# gatedriver_trafo_sma_compact_ACDC_smd.net
KiCad netlist of a schematic drawn in EAGLE
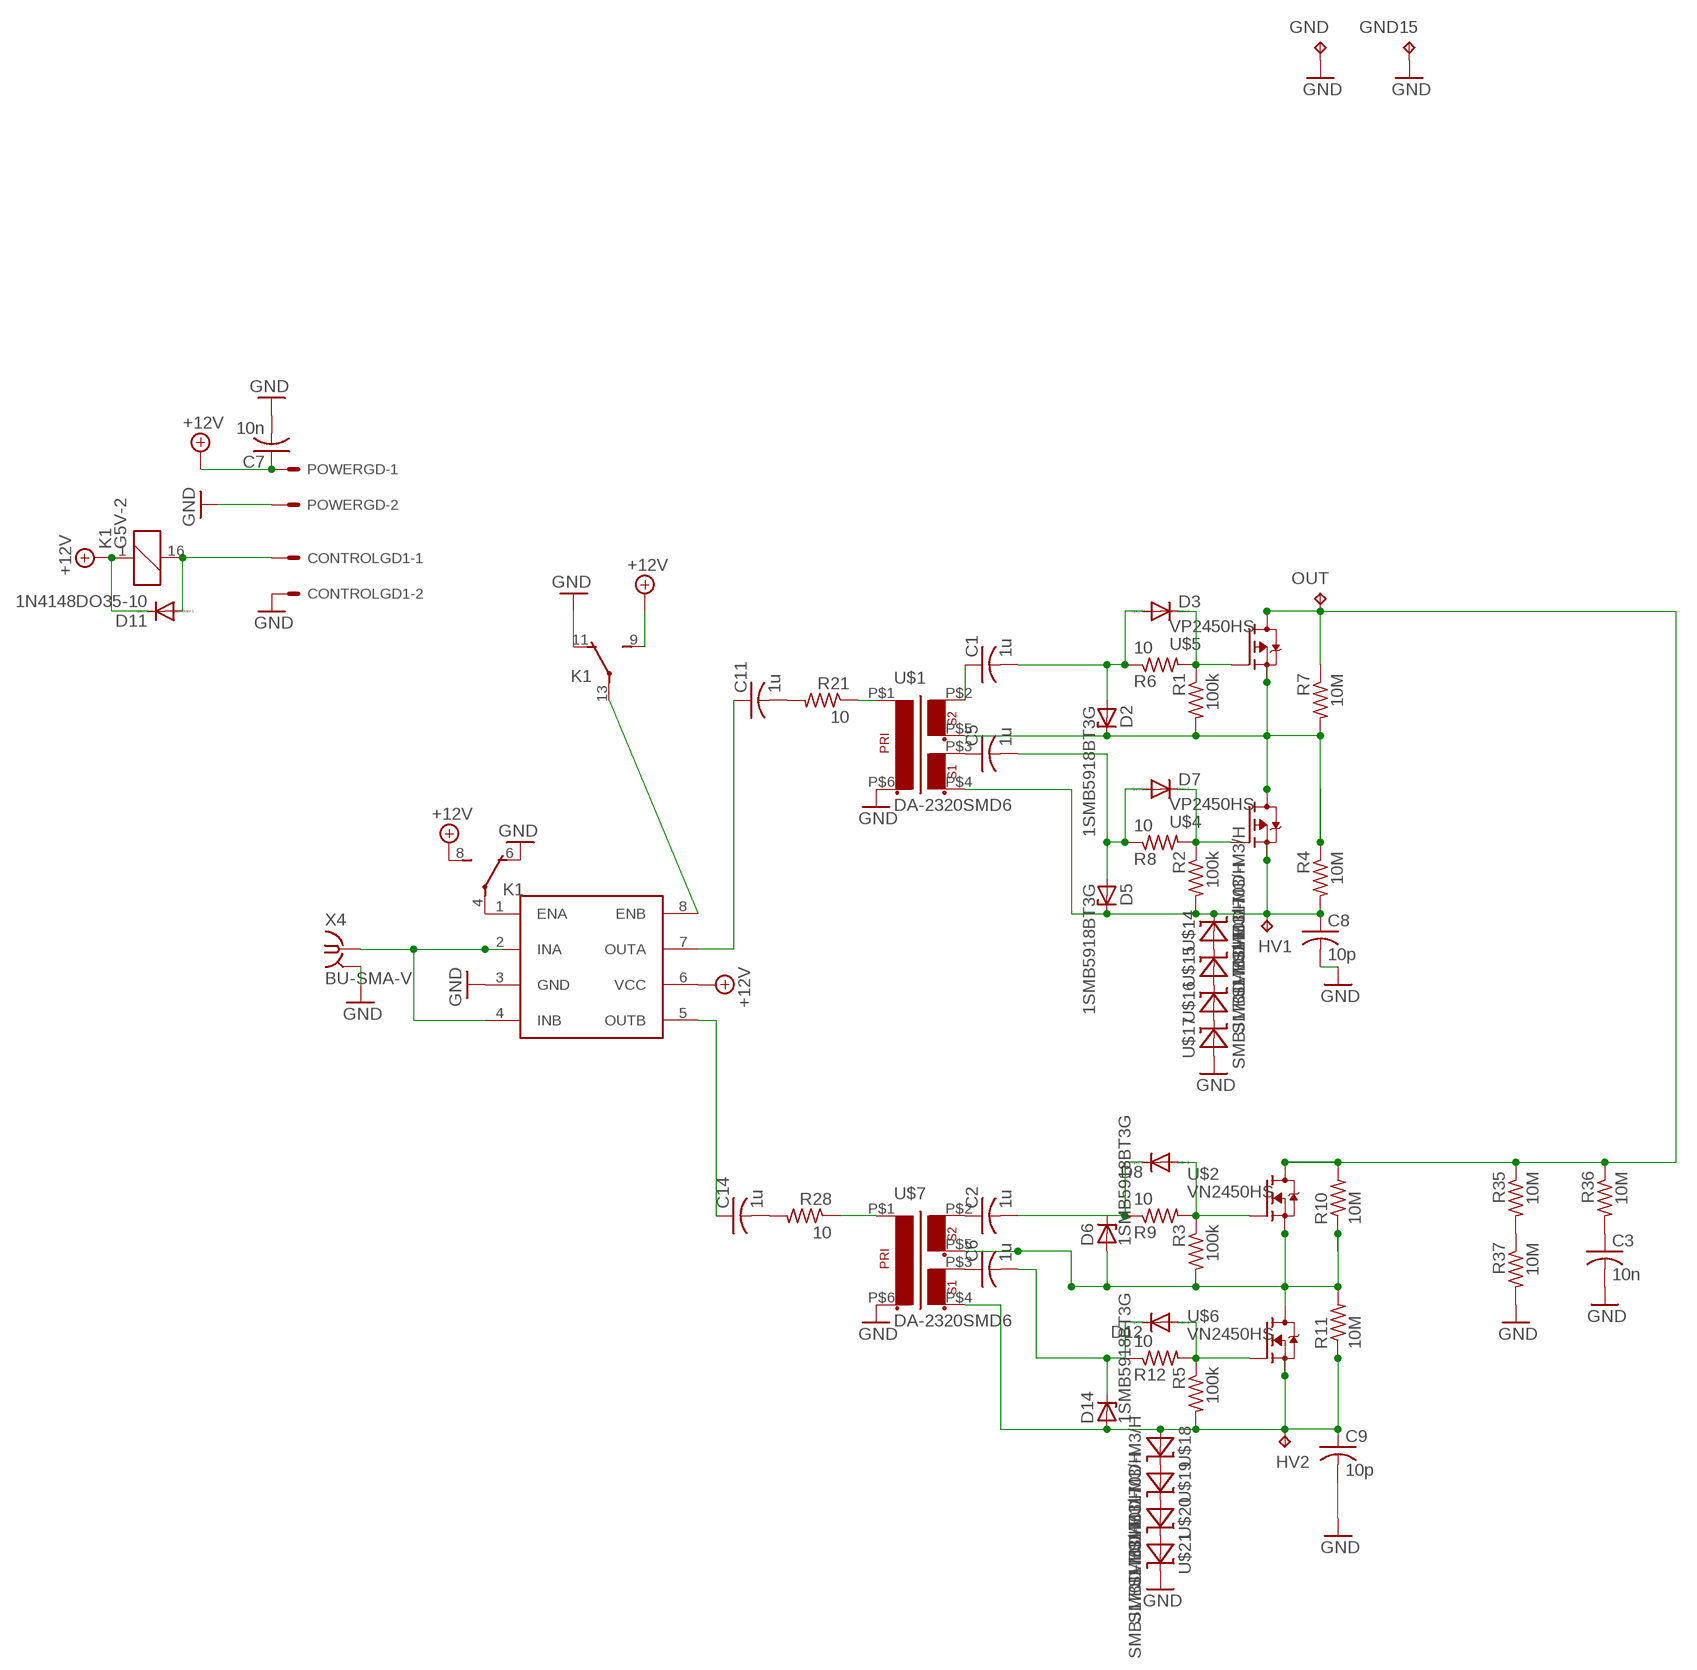
[diagram p0: schematic, sheet 1]

(export (version "E")
  (design (tool "Eeschema 10.0.6"))
  (components
    (comp (ref "C1")
      (value "1u")
      (footprint "eagle-import:C0805")
      (libsource (lib "eagle-import") (part "resistor_C-USC0805"))
    )
    (comp (ref "C2")
      (value "1u")
      (footprint "eagle-import:C0805")
      (libsource (lib "eagle-import") (part "resistor_C-USC0805"))
    )
    (comp (ref "C3")
      (value "10n")
      (footprint "eagle-import:C0805")
      (libsource (lib "eagle-import") (part "resistor_C-USC0805"))
    )
    (comp (ref "C5")
      (value "1u")
      (footprint "eagle-import:C0805")
      (libsource (lib "eagle-import") (part "resistor_C-USC0805"))
    )
    (comp (ref "C6")
      (value "1u")
      (footprint "eagle-import:C0805")
      (libsource (lib "eagle-import") (part "resistor_C-USC0805"))
    )
    (comp (ref "C7")
      (value "10n")
      (footprint "eagle-import:C050-030X075")
      (libsource (lib "eagle-import") (part "C-US050-030X075"))
    )
    (comp (ref "C8")
      (value "10p")
      (footprint "eagle-import:C102-064X133")
      (libsource (lib "eagle-import") (part "resistor_C-US102-064X133"))
    )
    (comp (ref "C9")
      (value "10p")
      (footprint "eagle-import:C102-064X133")
      (libsource (lib "eagle-import") (part "resistor_C-US102-064X133"))
    )
    (comp (ref "C11")
      (value "1u")
      (footprint "eagle-import:C0805")
      (libsource (lib "eagle-import") (part "resistor_C-USC0805"))
    )
    (comp (ref "C14")
      (value "1u")
      (footprint "eagle-import:C0805")
      (libsource (lib "eagle-import") (part "resistor_C-USC0805"))
    )
    (comp (ref "CONTROLGD1")
      (value "KK-156-2")
      (footprint "eagle-import:KK-156-2")
      (libsource (lib "eagle-import") (part "KK-156-2"))
    )
    (comp (ref "D2")
      (value "1SMB5918BT3G")
      (footprint "eagle-import:SMB")
      (libsource (lib "eagle-import") (part "ZENER-DIODESMB"))
    )
    (comp (ref "D3")
      (value "DIODE-SMB")
      (footprint "eagle-import:SMB")
      (libsource (lib "eagle-import") (part "DIODE-SMB"))
    )
    (comp (ref "D5")
      (value "1SMB5918BT3G")
      (footprint "eagle-import:SMB")
      (libsource (lib "eagle-import") (part "ZENER-DIODESMB"))
    )
    (comp (ref "D6")
      (value "1SMB5918BT3G")
      (footprint "eagle-import:SMB")
      (libsource (lib "eagle-import") (part "ZENER-DIODESMB"))
    )
    (comp (ref "D7")
      (value "DIODE-SMB")
      (footprint "eagle-import:SMB")
      (libsource (lib "eagle-import") (part "DIODE-SMB"))
    )
    (comp (ref "D8")
      (value "DIODE-SMB")
      (footprint "eagle-import:SMB")
      (libsource (lib "eagle-import") (part "DIODE-SMB"))
    )
    (comp (ref "D11")
      (value "1N4148DO35-10")
      (footprint "eagle-import:DO35-10")
      (libsource (lib "eagle-import") (part "1N4148DO35-10"))
    )
    (comp (ref "D12")
      (value "DIODE-SMB")
      (footprint "eagle-import:SMB")
      (libsource (lib "eagle-import") (part "DIODE-SMB"))
    )
    (comp (ref "D14")
      (value "1SMB5918BT3G")
      (footprint "eagle-import:SMB")
      (libsource (lib "eagle-import") (part "ZENER-DIODESMB"))
    )
    (comp (ref "GND")
      (value "TPPAD1-20Y")
      (footprint "eagle-import:P1-20Y")
      (libsource (lib "eagle-import") (part "TPPAD1-20Y"))
    )
    (comp (ref "GND15")
      (value "TPPAD1-20Y")
      (footprint "eagle-import:P1-20Y")
      (libsource (lib "eagle-import") (part "TPPAD1-20Y"))
    )
    (comp (ref "HV1")
      (value "TPPAD1-20Y")
      (footprint "eagle-import:P1-20Y")
      (libsource (lib "eagle-import") (part "TPPAD1-20Y"))
    )
    (comp (ref "HV2")
      (value "TPPAD1-20Y")
      (footprint "eagle-import:P1-20Y")
      (libsource (lib "eagle-import") (part "TPPAD1-20Y"))
    )
    (comp (ref "K1")
      (value "G5V-2")
      (footprint "eagle-import:G5V-2")
      (fields (field (name "MPN") "G5V-2 5DC"))
      (libsource (lib "eagle-import") (part "G5V-2"))
    )
    (comp (ref "OUT")
      (value "TPPAD1-20Y")
      (footprint "eagle-import:P1-20Y")
      (libsource (lib "eagle-import") (part "TPPAD1-20Y"))
    )
    (comp (ref "POWERGD")
      (value "KK-156-2")
      (footprint "eagle-import:KK-156-2")
      (libsource (lib "eagle-import") (part "KK-156-2"))
    )
    (comp (ref "R1")
      (value "100k")
      (footprint "eagle-import:R0805")
      (libsource (lib "eagle-import") (part "R-US_R0805"))
    )
    (comp (ref "R2")
      (value "100k")
      (footprint "eagle-import:R0805")
      (libsource (lib "eagle-import") (part "R-US_R0805"))
    )
    (comp (ref "R3")
      (value "100k")
      (footprint "eagle-import:R0805")
      (libsource (lib "eagle-import") (part "R-US_R0805"))
    )
    (comp (ref "R4")
      (value "10M")
      (footprint "eagle-import:R2512")
      (libsource (lib "eagle-import") (part "R-US_R2512"))
    )
    (comp (ref "R5")
      (value "100k")
      (footprint "eagle-import:R0805")
      (libsource (lib "eagle-import") (part "R-US_R0805"))
    )
    (comp (ref "R6")
      (value "10")
      (footprint "eagle-import:R0805")
      (libsource (lib "eagle-import") (part "R-US_R0805"))
    )
    (comp (ref "R7")
      (value "10M")
      (footprint "eagle-import:R2512")
      (libsource (lib "eagle-import") (part "R-US_R2512"))
    )
    (comp (ref "R8")
      (value "10")
      (footprint "eagle-import:R0805")
      (libsource (lib "eagle-import") (part "R-US_R0805"))
    )
    (comp (ref "R9")
      (value "10")
      (footprint "eagle-import:R0805")
      (libsource (lib "eagle-import") (part "R-US_R0805"))
    )
    (comp (ref "R10")
      (value "10M")
      (footprint "eagle-import:R2512")
      (libsource (lib "eagle-import") (part "R-US_R2512"))
    )
    (comp (ref "R11")
      (value "10M")
      (footprint "eagle-import:R2512")
      (libsource (lib "eagle-import") (part "R-US_R2512"))
    )
    (comp (ref "R12")
      (value "10")
      (footprint "eagle-import:R0805")
      (libsource (lib "eagle-import") (part "R-US_R0805"))
    )
    (comp (ref "R21")
      (value "10")
      (footprint "eagle-import:R0805")
      (libsource (lib "eagle-import") (part "R-US_R0805"))
    )
    (comp (ref "R28")
      (value "10")
      (footprint "eagle-import:R0805")
      (libsource (lib "eagle-import") (part "R-US_R0805"))
    )
    (comp (ref "R35")
      (value "10M")
      (footprint "eagle-import:R2512")
      (libsource (lib "eagle-import") (part "R-US_R2512"))
    )
    (comp (ref "R36")
      (value "10M")
      (footprint "eagle-import:R2512")
      (libsource (lib "eagle-import") (part "R-US_R2512"))
    )
    (comp (ref "R37")
      (value "10M")
      (footprint "eagle-import:R2512")
      (libsource (lib "eagle-import") (part "R-US_R2512"))
    )
    (comp (ref "U$1")
      (value "DA-2320SMD6")
      (footprint "eagle-import:SMD6")
      (libsource (lib "eagle-import") (part "DA-2320SMD6"))
    )
    (comp (ref "U$2")
      (value "VN2450HS")
      (footprint "eagle-import:SO89_HS")
      (libsource (lib "eagle-import") (part "VN2450HS"))
    )
    (comp (ref "U$3")
      (value "UCC27425")
      (footprint "eagle-import:DIL08")
      (libsource (lib "eagle-import") (part "UCC27425"))
    )
    (comp (ref "U$4")
      (value "VP2450HS")
      (footprint "eagle-import:SO89_HS")
      (libsource (lib "eagle-import") (part "VP2450HS"))
    )
    (comp (ref "U$5")
      (value "VP2450HS")
      (footprint "eagle-import:SO89_HS")
      (libsource (lib "eagle-import") (part "VP2450HS"))
    )
    (comp (ref "U$6")
      (value "VN2450HS")
      (footprint "eagle-import:SO89_HS")
      (libsource (lib "eagle-import") (part "VN2450HS"))
    )
    (comp (ref "U$7")
      (value "DA-2320SMD6")
      (footprint "eagle-import:SMD6")
      (libsource (lib "eagle-import") (part "DA-2320SMD6"))
    )
    (comp (ref "U$14")
      (value "SMBJ170D-M3/H")
      (footprint "eagle-import:DO214AA")
      (libsource (lib "eagle-import") (part "SMBJ170D-M3/H"))
    )
    (comp (ref "U$15")
      (value "SMBJ170D-M3/H")
      (footprint "eagle-import:DO214AA")
      (libsource (lib "eagle-import") (part "SMBJ170D-M3/H"))
    )
    (comp (ref "U$16")
      (value "SMBJ170D-M3/H")
      (footprint "eagle-import:DO214AA")
      (libsource (lib "eagle-import") (part "SMBJ170D-M3/H"))
    )
    (comp (ref "U$17")
      (value "SMBJ170D-M3/H")
      (footprint "eagle-import:DO214AA")
      (libsource (lib "eagle-import") (part "SMBJ170D-M3/H"))
    )
    (comp (ref "U$18")
      (value "SMBJ170D-M3/H")
      (footprint "eagle-import:DO214AA")
      (libsource (lib "eagle-import") (part "SMBJ170D-M3/H"))
    )
    (comp (ref "U$19")
      (value "SMBJ170D-M3/H")
      (footprint "eagle-import:DO214AA")
      (libsource (lib "eagle-import") (part "SMBJ170D-M3/H"))
    )
    (comp (ref "U$20")
      (value "SMBJ170D-M3/H")
      (footprint "eagle-import:DO214AA")
      (libsource (lib "eagle-import") (part "SMBJ170D-M3/H"))
    )
    (comp (ref "U$21")
      (value "SMBJ170D-M3/H")
      (footprint "eagle-import:DO214AA")
      (libsource (lib "eagle-import") (part "SMBJ170D-M3/H"))
    )
    (comp (ref "X4")
      (value "BU-SMA-V")
      (footprint "eagle-import:BU-SMA-V")
      (libsource (lib "eagle-import") (part "BU-SMA-V"))
    )
  )
  (nets
    (net (code "1") (name "+12V") (class "Default")
      (node (ref "C7") (pin "1") (pinfunction "1_1") (pintype "passive"))
      (node (ref "D11") (pin "C") (pinfunction "C_C") (pintype "passive"))
      (node (ref "K1") (pin "1") (pinfunction "1_1") (pintype "passive"))
      (node (ref "K1") (pin "8") (pinfunction "S_8") (pintype "passive"))
      (node (ref "K1") (pin "9") (pinfunction "S_9") (pintype "passive"))
      (node (ref "POWERGD") (pin "1") (pinfunction "S_1") (pintype "passive"))
      (node (ref "U$3") (pin "6") (pinfunction "VCC_6") (pintype "bidirectional"))
    )
    (net (code "2") (name "GND") (class "Default")
      (node (ref "C3") (pin "2") (pinfunction "2_2") (pintype "passive"))
      (node (ref "C7") (pin "2") (pinfunction "2_2") (pintype "passive"))
      (node (ref "C8") (pin "2") (pinfunction "2_2") (pintype "passive"))
      (node (ref "C9") (pin "2") (pinfunction "2_2") (pintype "passive"))
      (node (ref "CONTROLGD1") (pin "2") (pinfunction "S_2") (pintype "passive"))
      (node (ref "GND") (pin "TP") (pinfunction "TP_TP") (pintype "input"))
      (node (ref "GND15") (pin "TP") (pinfunction "TP_TP") (pintype "input"))
      (node (ref "K1") (pin "11") (pinfunction "O_11") (pintype "passive"))
      (node (ref "K1") (pin "6") (pinfunction "O_6") (pintype "passive"))
      (node (ref "POWERGD") (pin "2") (pinfunction "S_2") (pintype "passive"))
      (node (ref "R37") (pin "2") (pinfunction "2_2") (pintype "passive"))
      (node (ref "U$1") (pin "P$6") (pinfunction "2_P$6") (pintype "passive"))
      (node (ref "U$17") (pin "A") (pinfunction "A_A") (pintype "passive"))
      (node (ref "U$21") (pin "C") (pinfunction "C_C") (pintype "passive"))
      (node (ref "U$3") (pin "3") (pinfunction "GND_3") (pintype "bidirectional"))
      (node (ref "U$7") (pin "P$6") (pinfunction "2_P$6") (pintype "passive"))
      (node (ref "X4") (pin "2") (pinfunction "2_2") (pintype "passive"))
      (node (ref "X4") (pin "3") (pinfunction "2_3") (pintype "passive"))
      (node (ref "X4") (pin "4") (pinfunction "2_4") (pintype "passive"))
      (node (ref "X4") (pin "5") (pinfunction "2_5") (pintype "passive"))
    )
    (net (code "3") (name "Net-(C1-Pad2)") (class "Default")
      (node (ref "C1") (pin "2") (pinfunction "2_2") (pintype "passive"))
      (node (ref "D2") (pin "A") (pinfunction "A_A") (pintype "passive"))
      (node (ref "D3") (pin "A") (pinfunction "A_A") (pintype "passive"))
      (node (ref "R6") (pin "1") (pinfunction "1_1") (pintype "passive"))
    )
    (net (code "4") (name "Net-(C2-Pad2)") (class "Default")
      (node (ref "C2") (pin "2") (pinfunction "2_2") (pintype "passive"))
      (node (ref "D6") (pin "C") (pinfunction "C_C") (pintype "passive"))
      (node (ref "D8") (pin "C") (pinfunction "C_C") (pintype "passive"))
      (node (ref "R9") (pin "1") (pinfunction "1_1") (pintype "passive"))
    )
    (net (code "5") (name "Net-(C3-Pad1)") (class "Default")
      (node (ref "C3") (pin "1") (pinfunction "1_1") (pintype "passive"))
      (node (ref "R36") (pin "2") (pinfunction "2_2") (pintype "passive"))
    )
    (net (code "6") (name "Net-(C5-Pad2)") (class "Default")
      (node (ref "C5") (pin "2") (pinfunction "2_2") (pintype "passive"))
      (node (ref "D5") (pin "A") (pinfunction "A_A") (pintype "passive"))
      (node (ref "D7") (pin "A") (pinfunction "A_A") (pintype "passive"))
      (node (ref "R8") (pin "1") (pinfunction "1_1") (pintype "passive"))
    )
    (net (code "7") (name "Net-(C6-Pad2)") (class "Default")
      (node (ref "C6") (pin "2") (pinfunction "2_2") (pintype "passive"))
      (node (ref "D12") (pin "C") (pinfunction "C_C") (pintype "passive"))
      (node (ref "D14") (pin "C") (pinfunction "C_C") (pintype "passive"))
      (node (ref "R12") (pin "1") (pinfunction "1_1") (pintype "passive"))
    )
    (net (code "8") (name "Net-(C11-Pad2)") (class "Default")
      (node (ref "C11") (pin "2") (pinfunction "2_2") (pintype "passive"))
      (node (ref "R21") (pin "2") (pinfunction "2_2") (pintype "passive"))
    )
    (net (code "9") (name "Net-(C14-Pad2)") (class "Default")
      (node (ref "C14") (pin "2") (pinfunction "2_2") (pintype "passive"))
      (node (ref "R28") (pin "2") (pinfunction "2_2") (pintype "passive"))
    )
    (net (code "10") (name "Net-(CONTROLGD1A-S)") (class "Default")
      (node (ref "CONTROLGD1") (pin "1") (pinfunction "S_1") (pintype "passive"))
      (node (ref "D11") (pin "A") (pinfunction "A_A") (pintype "passive"))
      (node (ref "K1") (pin "16") (pinfunction "2_16") (pintype "passive"))
    )
    (net (code "11") (name "Net-(K1A-P)") (class "Default")
      (node (ref "K1") (pin "4") (pinfunction "P_4") (pintype "passive"))
      (node (ref "U$3") (pin "1") (pinfunction "ENA_1") (pintype "bidirectional"))
    )
    (net (code "12") (name "Net-(K1B-P)") (class "Default")
      (node (ref "K1") (pin "13") (pinfunction "P_13") (pintype "passive"))
      (node (ref "U$3") (pin "8") (pinfunction "ENB_8") (pintype "bidirectional"))
    )
    (net (code "13") (name "Net-(OUT-PadTP)") (class "Default")
      (node (ref "OUT") (pin "TP") (pinfunction "TP_TP") (pintype "input"))
      (node (ref "R10") (pin "2") (pinfunction "2_2") (pintype "passive"))
      (node (ref "R35") (pin "1") (pinfunction "1_1") (pintype "passive"))
      (node (ref "R36") (pin "1") (pinfunction "1_1") (pintype "passive"))
      (node (ref "R7") (pin "1") (pinfunction "1_1") (pintype "passive"))
      (node (ref "U$2") (pin "C") (pinfunction "D_C") (pintype "passive"))
      (node (ref "U$2") (pin "C@1") (pinfunction "D_C@1") (pintype "passive"))
      (node (ref "U$5") (pin "C") (pinfunction "D_C") (pintype "passive"))
      (node (ref "U$5") (pin "C@1") (pinfunction "D_C@1") (pintype "passive"))
    )
    (net (code "14") (name "Net-(R35-Pad2)") (class "Default")
      (node (ref "R35") (pin "2") (pinfunction "2_2") (pintype "passive"))
      (node (ref "R37") (pin "1") (pinfunction "1_1") (pintype "passive"))
    )
    (net (code "15") (name "Net-(U$1-1)") (class "Default")
      (node (ref "R21") (pin "1") (pinfunction "1_1") (pintype "passive"))
      (node (ref "U$1") (pin "P$1") (pinfunction "1_P$1") (pintype "passive"))
    )
    (net (code "16") (name "Net-(U$1-3)") (class "Default")
      (node (ref "C8") (pin "1") (pinfunction "1_1") (pintype "passive"))
      (node (ref "D5") (pin "C") (pinfunction "C_C") (pintype "passive"))
      (node (ref "HV1") (pin "TP") (pinfunction "TP_TP") (pintype "input"))
      (node (ref "R2") (pin "2") (pinfunction "2_2") (pintype "passive"))
      (node (ref "R4") (pin "2") (pinfunction "2_2") (pintype "passive"))
      (node (ref "U$1") (pin "P$4") (pinfunction "3_P$4") (pintype "passive"))
      (node (ref "U$14") (pin "C") (pinfunction "C_C") (pintype "passive"))
      (node (ref "U$4") (pin "E") (pinfunction "S_E") (pintype "passive"))
    )
    (net (code "17") (name "Net-(U$1-4)") (class "Default")
      (node (ref "C5") (pin "1") (pinfunction "1_1") (pintype "passive"))
      (node (ref "U$1") (pin "P$3") (pinfunction "4_P$3") (pintype "passive"))
    )
    (net (code "18") (name "Net-(U$1-5)") (class "Default")
      (node (ref "D2") (pin "C") (pinfunction "C_C") (pintype "passive"))
      (node (ref "R1") (pin "2") (pinfunction "2_2") (pintype "passive"))
      (node (ref "R4") (pin "1") (pinfunction "1_1") (pintype "passive"))
      (node (ref "R7") (pin "2") (pinfunction "2_2") (pintype "passive"))
      (node (ref "U$1") (pin "P$5") (pinfunction "5_P$5") (pintype "passive"))
      (node (ref "U$4") (pin "C") (pinfunction "D_C") (pintype "passive"))
      (node (ref "U$4") (pin "C@1") (pinfunction "D_C@1") (pintype "passive"))
      (node (ref "U$5") (pin "E") (pinfunction "S_E") (pintype "passive"))
    )
    (net (code "19") (name "Net-(U$1-6)") (class "Default")
      (node (ref "C1") (pin "1") (pinfunction "1_1") (pintype "passive"))
      (node (ref "U$1") (pin "P$2") (pinfunction "6_P$2") (pintype "passive"))
    )
    (net (code "20") (name "Net-(U$2-G)") (class "Default")
      (node (ref "D8") (pin "A") (pinfunction "A_A") (pintype "passive"))
      (node (ref "R3") (pin "1") (pinfunction "1_1") (pintype "passive"))
      (node (ref "R9") (pin "2") (pinfunction "2_2") (pintype "passive"))
      (node (ref "U$2") (pin "B") (pinfunction "G_B") (pintype "passive"))
    )
    (net (code "21") (name "Net-(U$2-S)") (class "Default")
      (node (ref "D6") (pin "A") (pinfunction "A_A") (pintype "passive"))
      (node (ref "R10") (pin "1") (pinfunction "1_1") (pintype "passive"))
      (node (ref "R11") (pin "2") (pinfunction "2_2") (pintype "passive"))
      (node (ref "R3") (pin "2") (pinfunction "2_2") (pintype "passive"))
      (node (ref "U$2") (pin "E") (pinfunction "S_E") (pintype "passive"))
      (node (ref "U$6") (pin "C") (pinfunction "D_C") (pintype "passive"))
      (node (ref "U$6") (pin "C@1") (pinfunction "D_C@1") (pintype "passive"))
      (node (ref "U$7") (pin "P$5") (pinfunction "5_P$5") (pintype "passive"))
    )
    (net (code "22") (name "Net-(U$3-INA)") (class "Default")
      (node (ref "U$3") (pin "2") (pinfunction "INA_2") (pintype "bidirectional"))
      (node (ref "U$3") (pin "4") (pinfunction "INB_4") (pintype "bidirectional"))
      (node (ref "X4") (pin "1") (pinfunction "1_1") (pintype "passive"))
    )
    (net (code "23") (name "Net-(U$3-OUTA)") (class "Default")
      (node (ref "C11") (pin "1") (pinfunction "1_1") (pintype "passive"))
      (node (ref "U$3") (pin "7") (pinfunction "OUTA_7") (pintype "bidirectional"))
    )
    (net (code "24") (name "Net-(U$3-OUTB)") (class "Default")
      (node (ref "C14") (pin "1") (pinfunction "1_1") (pintype "passive"))
      (node (ref "U$3") (pin "5") (pinfunction "OUTB_5") (pintype "bidirectional"))
    )
    (net (code "25") (name "Net-(U$4-G)") (class "Default")
      (node (ref "D7") (pin "C") (pinfunction "C_C") (pintype "passive"))
      (node (ref "R2") (pin "1") (pinfunction "1_1") (pintype "passive"))
      (node (ref "R8") (pin "2") (pinfunction "2_2") (pintype "passive"))
      (node (ref "U$4") (pin "B") (pinfunction "G_B") (pintype "passive"))
    )
    (net (code "26") (name "Net-(U$5-G)") (class "Default")
      (node (ref "D3") (pin "C") (pinfunction "C_C") (pintype "passive"))
      (node (ref "R1") (pin "1") (pinfunction "1_1") (pintype "passive"))
      (node (ref "R6") (pin "2") (pinfunction "2_2") (pintype "passive"))
      (node (ref "U$5") (pin "B") (pinfunction "G_B") (pintype "passive"))
    )
    (net (code "27") (name "Net-(U$6-G)") (class "Default")
      (node (ref "D12") (pin "A") (pinfunction "A_A") (pintype "passive"))
      (node (ref "R12") (pin "2") (pinfunction "2_2") (pintype "passive"))
      (node (ref "R5") (pin "1") (pinfunction "1_1") (pintype "passive"))
      (node (ref "U$6") (pin "B") (pinfunction "G_B") (pintype "passive"))
    )
    (net (code "28") (name "Net-(U$6-S)") (class "Default")
      (node (ref "C9") (pin "1") (pinfunction "1_1") (pintype "passive"))
      (node (ref "D14") (pin "A") (pinfunction "A_A") (pintype "passive"))
      (node (ref "HV2") (pin "TP") (pinfunction "TP_TP") (pintype "input"))
      (node (ref "R11") (pin "1") (pinfunction "1_1") (pintype "passive"))
      (node (ref "R5") (pin "2") (pinfunction "2_2") (pintype "passive"))
      (node (ref "U$18") (pin "A") (pinfunction "A_A") (pintype "passive"))
      (node (ref "U$6") (pin "E") (pinfunction "S_E") (pintype "passive"))
      (node (ref "U$7") (pin "P$4") (pinfunction "3_P$4") (pintype "passive"))
    )
    (net (code "29") (name "Net-(U$7-1)") (class "Default")
      (node (ref "R28") (pin "1") (pinfunction "1_1") (pintype "passive"))
      (node (ref "U$7") (pin "P$1") (pinfunction "1_P$1") (pintype "passive"))
    )
    (net (code "30") (name "Net-(U$7-4)") (class "Default")
      (node (ref "C6") (pin "1") (pinfunction "1_1") (pintype "passive"))
      (node (ref "U$7") (pin "P$3") (pinfunction "4_P$3") (pintype "passive"))
    )
    (net (code "31") (name "Net-(U$7-6)") (class "Default")
      (node (ref "C2") (pin "1") (pinfunction "1_1") (pintype "passive"))
      (node (ref "U$7") (pin "P$2") (pinfunction "6_P$2") (pintype "passive"))
    )
    (net (code "32") (name "Net-(U$14-PadA)") (class "Default")
      (node (ref "U$14") (pin "A") (pinfunction "A_A") (pintype "passive"))
      (node (ref "U$15") (pin "C") (pinfunction "C_C") (pintype "passive"))
    )
    (net (code "33") (name "Net-(U$15-PadA)") (class "Default")
      (node (ref "U$15") (pin "A") (pinfunction "A_A") (pintype "passive"))
      (node (ref "U$16") (pin "C") (pinfunction "C_C") (pintype "passive"))
    )
    (net (code "34") (name "Net-(U$16-PadA)") (class "Default")
      (node (ref "U$16") (pin "A") (pinfunction "A_A") (pintype "passive"))
      (node (ref "U$17") (pin "C") (pinfunction "C_C") (pintype "passive"))
    )
    (net (code "35") (name "Net-(U$18-PadC)") (class "Default")
      (node (ref "U$18") (pin "C") (pinfunction "C_C") (pintype "passive"))
      (node (ref "U$19") (pin "A") (pinfunction "A_A") (pintype "passive"))
    )
    (net (code "36") (name "Net-(U$19-PadC)") (class "Default")
      (node (ref "U$19") (pin "C") (pinfunction "C_C") (pintype "passive"))
      (node (ref "U$20") (pin "A") (pinfunction "A_A") (pintype "passive"))
    )
    (net (code "37") (name "Net-(U$20-PadC)") (class "Default")
      (node (ref "U$20") (pin "C") (pinfunction "C_C") (pintype "passive"))
      (node (ref "U$21") (pin "A") (pinfunction "A_A") (pintype "passive"))
    )
  )
)
